# PotsDuino.net
KiCad netlist of a schematic drawn in Altium Designer
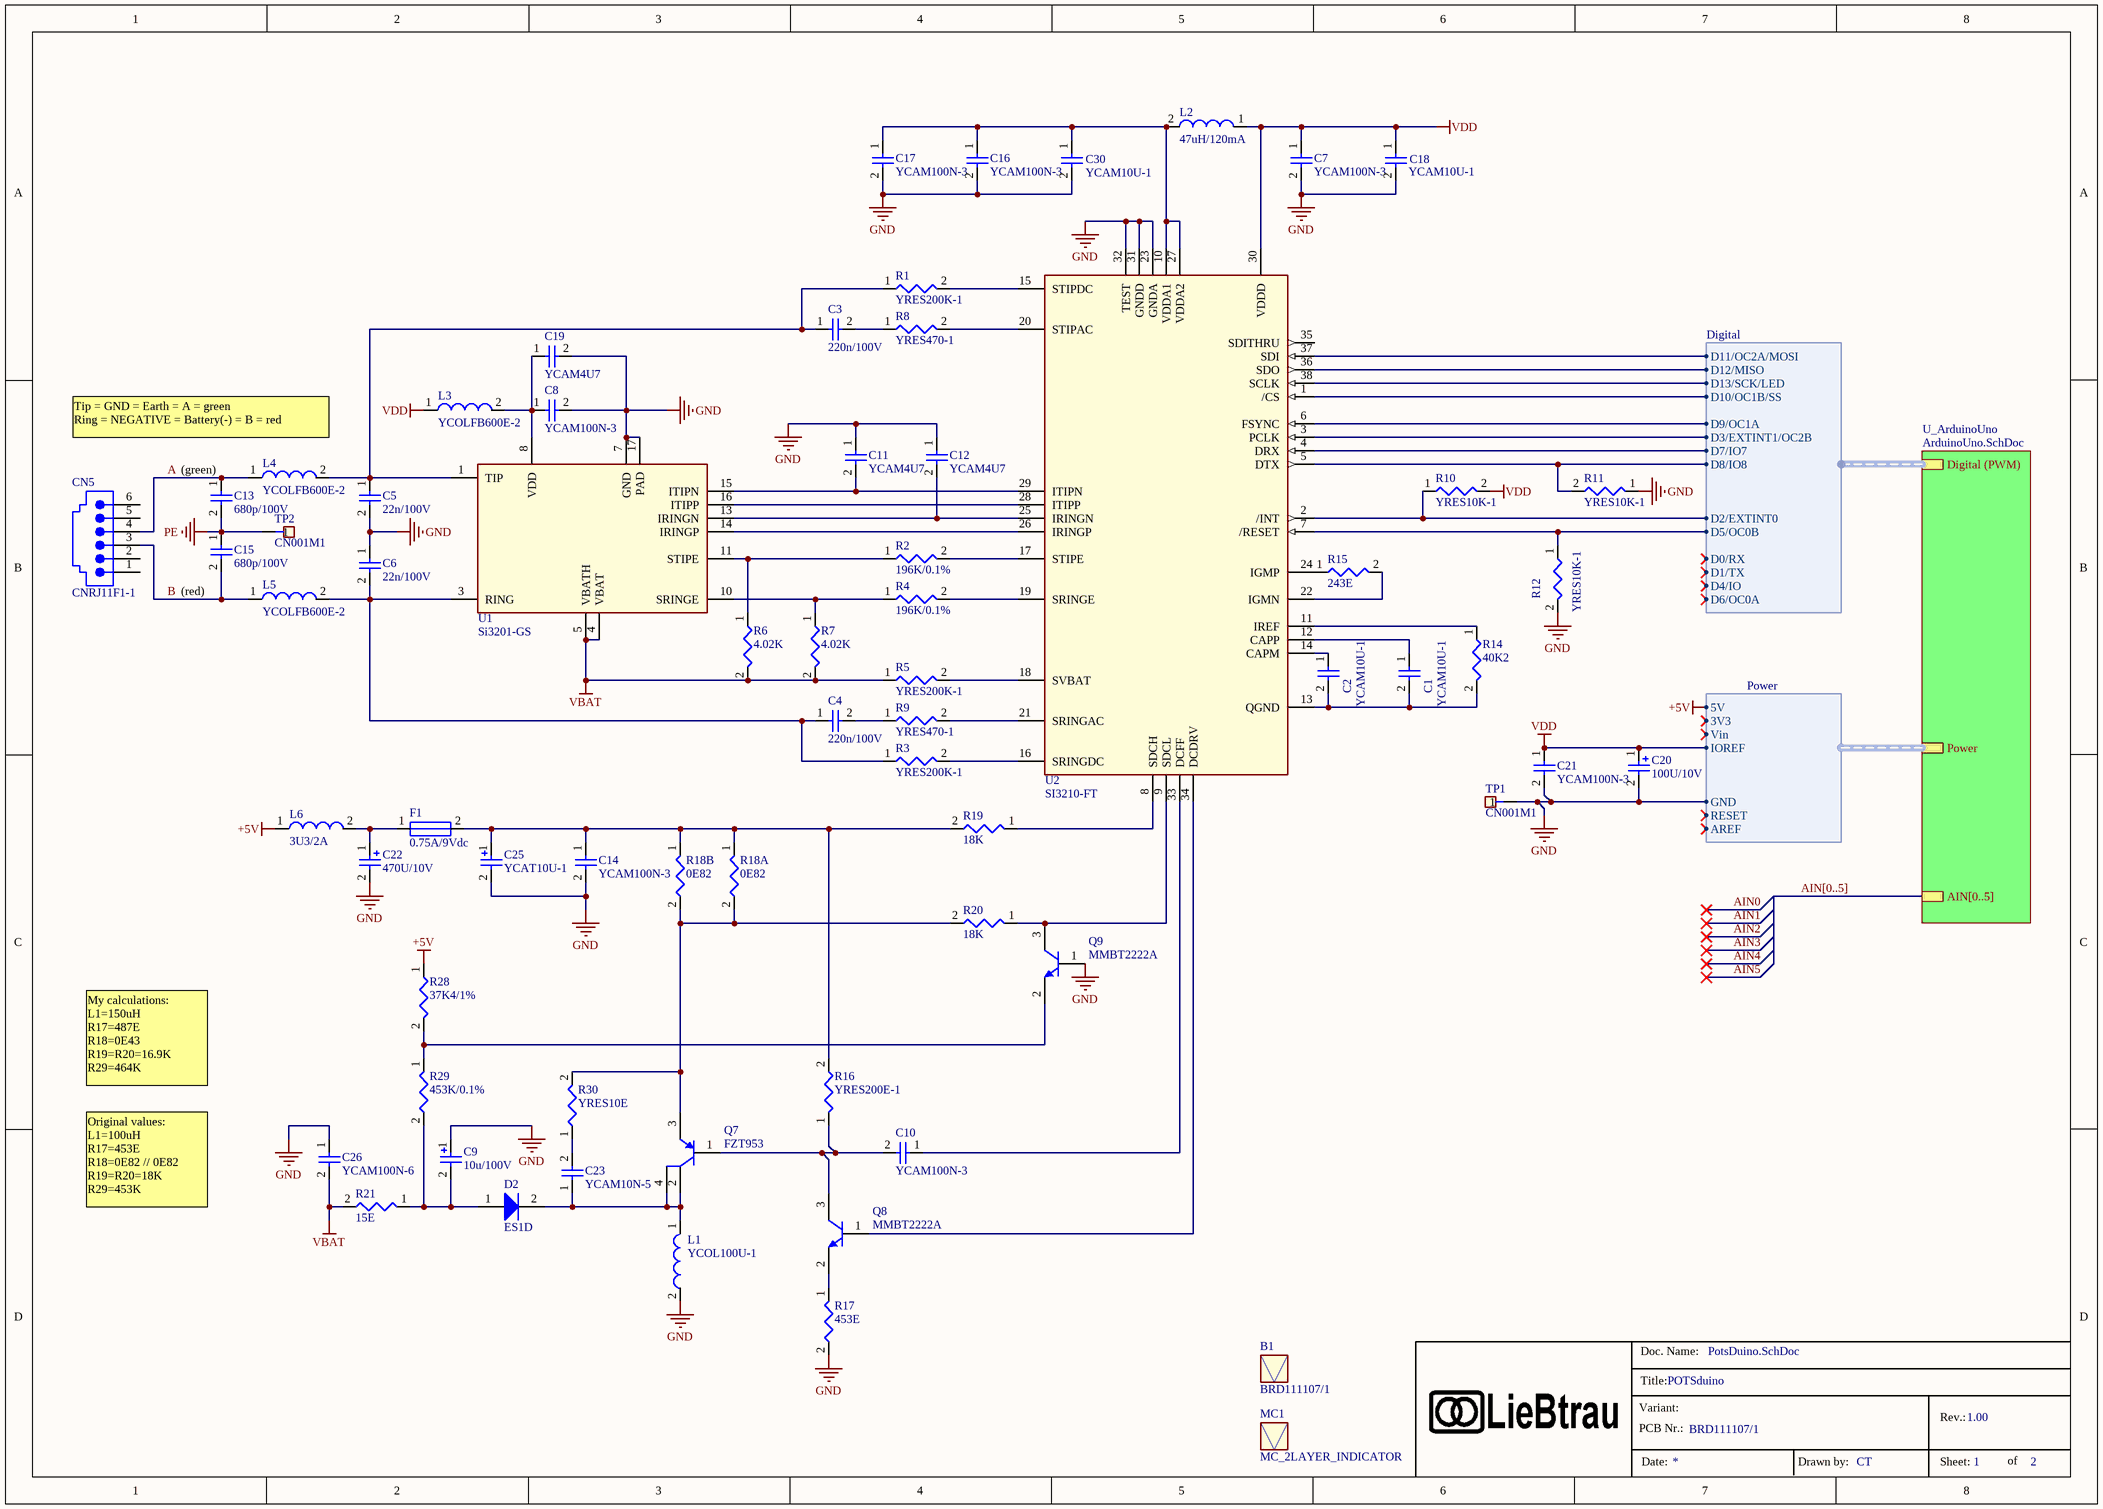
[diagram p0: PotsDuino.SchDoc]

(export (version "E")
  (design (tool "Eeschema 10.0.6"))
  (components
    (comp (ref "B1")
      (value "~")
      (footprint "=PCB_Nr")
      (fields (field (name "PART NUMBER") "BARE_PCB"))
      (libsource (lib "Testing") (part "BD_PCB"))
    )
    (comp (ref "C1") (value "YCAM10U-1") (footprint "CA_0805") (libsource (lib "Testing") (part "CA_NONPOL")))
    (comp (ref "C2") (value "YCAM10U-1") (footprint "CA_0805") (libsource (lib "Testing") (part "CA_NONPOL")))
    (comp (ref "C3")
      (value "220n/100V")
      (footprint "CA_0805")
      (fields (field (name "PART NUMBER") "MCCA000493") (field (name "MANUFACTURER") "Multicomp"))
      (libsource (lib "Testing") (part "CA_NONPOL"))
    )
    (comp (ref "C4")
      (value "220n/100V")
      (footprint "CA_0805")
      (fields (field (name "PART NUMBER") "MCCA000493") (field (name "MANUFACTURER") "Multicomp"))
      (libsource (lib "Testing") (part "CA_NONPOL"))
    )
    (comp (ref "C5")
      (value "22n/100V")
      (footprint "CA_0603")
      (fields (field (name "PART NUMBER") "C0603C223K1RACTU") (field (name "MANUFACTURER") "Kemet"))
      (libsource (lib "Testing") (part "CA_NONPOL"))
    )
    (comp (ref "C6")
      (value "22n/100V")
      (footprint "CA_0603")
      (fields (field (name "PART NUMBER") "C0603C223K1RACTU") (field (name "MANUFACTURER") "Kemet"))
      (libsource (lib "Testing") (part "CA_NONPOL"))
    )
    (comp (ref "C7")
      (value "YCAM100N-3")
      (footprint "CA_0603")
      (libsource (lib "Testing") (part "CA_NONPOL"))
    )
    (comp (ref "C8")
      (value "YCAM100N-3")
      (footprint "CA_0603")
      (libsource (lib "Testing") (part "CA_NONPOL"))
    )
    (comp (ref "C9")
      (value "10u/100V")
      (footprint "CA_CANTHD63P25_H110_R")
      (fields (field (name "PART NUMBER") "100YXF10MEFC6.3X11") (field (name "MANUFACTURER") "Rubycon"))
      (libsource (lib "Testing") (part "CA_POL"))
    )
    (comp (ref "C10")
      (value "YCAM100N-3")
      (footprint "CA_0603")
      (libsource (lib "Testing") (part "CA_NONPOL"))
    )
    (comp (ref "C11") (value "YCAM4U7") (footprint "CA_1206") (libsource (lib "Testing") (part "CA_NONPOL")))
    (comp (ref "C12") (value "YCAM4U7") (footprint "CA_1206") (libsource (lib "Testing") (part "CA_NONPOL")))
    (comp (ref "C13")
      (value "680p/100V")
      (footprint "CA_0603")
      (fields (field (name "PART NUMBER") "C0603C681J1GACTU") (field (name "MANUFACTURER") "Kemet"))
      (libsource (lib "Testing") (part "CA_NONPOL"))
    )
    (comp (ref "C14")
      (value "YCAM100N-3")
      (footprint "CA_0603")
      (libsource (lib "Testing") (part "CA_NONPOL"))
    )
    (comp (ref "C15")
      (value "680p/100V")
      (footprint "CA_0603")
      (fields (field (name "PART NUMBER") "C0603C681J1GACTU") (field (name "MANUFACTURER") "Kemet"))
      (libsource (lib "Testing") (part "CA_NONPOL"))
    )
    (comp (ref "C16")
      (value "YCAM100N-3")
      (footprint "CA_0603")
      (libsource (lib "Testing") (part "CA_NONPOL"))
    )
    (comp (ref "C17")
      (value "YCAM100N-3")
      (footprint "CA_0603")
      (libsource (lib "Testing") (part "CA_NONPOL"))
    )
    (comp (ref "C18")
      (value "YCAM10U-1")
      (footprint "CA_0805")
      (libsource (lib "Testing") (part "CA_NONPOL"))
    )
    (comp (ref "C19") (value "YCAM4U7") (footprint "CA_1206") (libsource (lib "Testing") (part "CA_NONPOL")))
    (comp (ref "C20")
      (value "100U/10V")
      (footprint "CA_CANTHD50P20_H110")
      (fields (field (name "PART NUMBER") "MCGPR10V107M5X11") (field (name "MANUFACTURER") "Multicomp"))
      (libsource (lib "Testing") (part "CA_POL"))
    )
    (comp (ref "C21")
      (value "YCAM100N-3")
      (footprint "CA_0603")
      (libsource (lib "Testing") (part "CA_NONPOL"))
    )
    (comp (ref "C22")
      (value "470U/10V")
      (footprint "CA_CANTHD80P35_H110")
      (fields (field (name "PART NUMBER") "MCGPR10V477M8X11") (field (name "MANUFACTURER") "Multicomp"))
      (libsource (lib "Testing") (part "CA_POL"))
    )
    (comp (ref "C23")
      (value "YCAM10N-5")
      (footprint "CA_1206")
      (fields (field (name "MANUFACTURER") "Yageo (Phycomp)"))
      (libsource (lib "Testing") (part "CA_NONPOL"))
    )
    (comp (ref "C25")
      (value "YCAT10U-1")
      (footprint "CA_1210_H21")
      (libsource (lib "Testing") (part "CA_POL"))
    )
    (comp (ref "C26")
      (value "YCAM100N-6")
      (footprint "CA_0805")
      (libsource (lib "Testing") (part "CA_NONPOL"))
    )
    (comp (ref "C30")
      (value "YCAM10U-1")
      (footprint "CA_0805")
      (libsource (lib "Testing") (part "CA_NONPOL"))
    )
    (comp (ref "CN5")
      (value "CNRJ11F1-1")
      (footprint "CN_MODJACK_6P")
      (libsource (lib "Testing") (part "CN_MODJACK_6P"))
    )
    (comp (ref "D2")
      (value "ES1D")
      (footprint "DI_DO-214AC")
      (description "1 Amp General Purpose Rectifier")
      (fields (field (name "MANUFACTURER") "Fairchild Semiconductor"))
      (libsource (lib "Testing") (part "DI_DIODE"))
    )
    (comp (ref "F1")
      (value "0.75A/9Vdc")
      (footprint "RE_0805")
      (fields (field (name "PART NUMBER") "MC36210") (field (name "MANUFACTURER") "Multicomp"))
      (libsource (lib "Testing") (part "FU_FUSE"))
    )
    (comp (ref "L1")
      (value "YCOL100U-1")
      (footprint "CL_WE-PD4")
      (fields (field (name "MANUFACTURER") "Wuerth Elektronik"))
      (libsource (lib "Testing") (part "CL_COIL"))
    )
    (comp (ref "L2")
      (value "47uH/120mA")
      (footprint "CL_0805")
      (fields (field (name "PART NUMBER") "L0805C470MDWIT") (field (name "MANUFACTURER") "Kemet"))
      (libsource (lib "Testing") (part "CL_COIL"))
    )
    (comp (ref "L3")
      (value "YCOLFB600E-2")
      (footprint "CL_0603")
      (fields (field (name "MANUFACTURER") "Murata"))
      (libsource (lib "") (part "CL_COIL_1"))
    )
    (comp (ref "L4")
      (value "YCOLFB600E-2")
      (footprint "CL_0603")
      (fields (field (name "MANUFACTURER") "Murata"))
      (libsource (lib "") (part "CL_COIL_1"))
    )
    (comp (ref "L5")
      (value "YCOLFB600E-2")
      (footprint "CL_0603")
      (fields (field (name "MANUFACTURER") "Murata"))
      (libsource (lib "") (part "CL_COIL_1"))
    )
    (comp (ref "L6")
      (value "3U3/2A")
      (footprint "CL_BOURNS_SDR0604_58x60")
      (fields (field (name "PART NUMBER") "MCSDC0604-3R3MU") (field (name "MANUFACTURER") "Multicomp"))
      (libsource (lib "") (part "CL_COIL_1"))
    )
    (comp (ref "MC1")
      (value "MC_2LAYER_INDICATOR")
      (footprint "MC_2LAYER_INDICATOR")
      (libsource (lib "Testing") (part "MC_MechPart_No_BOM"))
    )
    (comp (ref "Q7")
      (value "FZT953")
      (footprint "SC_SOT223")
      (description "Amplifier Transistor NPN Silicon")
      (fields (field (name "MANUFACTURER") "Diodes Inc."))
      (libsource (lib "Testing") (part "TR_PNP_1"))
    )
    (comp (ref "Q8")
      (value "MMBT2222A")
      (footprint "SC_SOT23")
      (description "Amplifier Transistor NPN Silicon")
      (fields (field (name "MANUFACTURER") "Fairchild Semiconductor"))
      (libsource (lib "Testing") (part "TR_NPN_1"))
    )
    (comp (ref "Q9")
      (value "MMBT2222A")
      (footprint "SC_SOT23")
      (description "Amplifier Transistor NPN Silicon")
      (fields (field (name "MANUFACTURER") "Fairchild Semiconductor"))
      (libsource (lib "Testing") (part "TR_NPN_1"))
    )
    (comp (ref "R1")
      (value "YRES200K-1")
      (footprint "RE_0603")
      (description "Resistor")
      (libsource (lib "Testing") (part "RE_RES"))
    )
    (comp (ref "R2")
      (value "196K/0.1%")
      (footprint "RE_0603")
      (description "Resistor")
      (fields
        (field (name "PART NUMBER") "ERA3AEB1963V")
        (field (name "MANUFACTURER") "Panasonic Electronic Components")
      )
      (libsource (lib "Testing") (part "RE_RES"))
    )
    (comp (ref "R3")
      (value "YRES200K-1")
      (footprint "RE_0603")
      (description "Resistor")
      (libsource (lib "Testing") (part "RE_RES"))
    )
    (comp (ref "R4")
      (value "196K/0.1%")
      (footprint "RE_0603")
      (description "Resistor")
      (fields
        (field (name "PART NUMBER") "ERA3AEB1963V")
        (field (name "MANUFACTURER") "Panasonic Electronic Components")
      )
      (libsource (lib "Testing") (part "RE_RES"))
    )
    (comp (ref "R5")
      (value "YRES200K-1")
      (footprint "RE_0603")
      (description "Resistor")
      (libsource (lib "Testing") (part "RE_RES"))
    )
    (comp (ref "R6")
      (value "4.02K")
      (footprint "RE_1206")
      (description "Resistor")
      (fields (field (name "PART NUMBER") "CRCW12064K02FKEA") (field (name "MANUFACTURER") "Vishay Draloric"))
      (libsource (lib "Testing") (part "RE_RES"))
    )
    (comp (ref "R7")
      (value "4.02K")
      (footprint "RE_1206")
      (description "Resistor")
      (fields (field (name "PART NUMBER") "CRCW12064K02FKEA") (field (name "MANUFACTURER") "Vishay Draloric"))
      (libsource (lib "Testing") (part "RE_RES"))
    )
    (comp (ref "R8")
      (value "YRES470-1")
      (footprint "RE_0603")
      (description "Resistor")
      (libsource (lib "Testing") (part "RE_RES"))
    )
    (comp (ref "R9")
      (value "YRES470-1")
      (footprint "RE_0603")
      (description "Resistor")
      (libsource (lib "Testing") (part "RE_RES"))
    )
    (comp (ref "R10")
      (value "YRES10K-1")
      (footprint "RE_0603")
      (description "Resistor")
      (libsource (lib "Testing") (part "RE_RES"))
    )
    (comp (ref "R11")
      (value "YRES10K-1")
      (footprint "RE_0603")
      (description "Resistor")
      (libsource (lib "Testing") (part "RE_RES"))
    )
    (comp (ref "R12")
      (value "YRES10K-1")
      (footprint "RE_0603")
      (description "Resistor")
      (libsource (lib "Testing") (part "RE_RES"))
    )
    (comp (ref "R14")
      (value "40K2")
      (footprint "RE_0603")
      (description "Resistor")
      (fields (field (name "PART NUMBER") "MC 0.063W 0603 1% 40K2") (field (name "MANUFACTURER") "Multicomp"))
      (libsource (lib "Testing") (part "RE_RES"))
    )
    (comp (ref "R15")
      (value "243E")
      (footprint "RE_0603")
      (description "Resistor")
      (fields (field (name "PART NUMBER") "MC 0.063W 0603 1% 243R") (field (name "MANUFACTURER") "Multicomp"))
      (libsource (lib "Testing") (part "RE_RES"))
    )
    (comp (ref "R16")
      (value "YRES200E-1")
      (footprint "RE_0603")
      (description "Resistor")
      (libsource (lib "Testing") (part "RE_RES"))
    )
    (comp (ref "R17")
      (value "453E")
      (footprint "RE_0805")
      (description "Resistor")
      (fields (field (name "PART NUMBER") "MCTC0525B4530T5E") (field (name "MANUFACTURER") "Multicomp"))
      (libsource (lib "Testing") (part "RE_RES"))
    )
    (comp (ref "R18A")
      (value "0E82")
      (footprint "RE_0805")
      (description "Resistor")
      (fields
        (field (name "PART NUMBER") "ERJ6RQFR82V")
        (field (name "MANUFACTURER") "Panasonic Electronic Components")
      )
      (libsource (lib "Testing") (part "RE_RES"))
    )
    (comp (ref "R18B")
      (value "0E82")
      (footprint "RE_0805")
      (description "Resistor")
      (fields
        (field (name "PART NUMBER") "ERJ6RQFR82V")
        (field (name "MANUFACTURER") "Panasonic Electronic Components")
      )
      (libsource (lib "Testing") (part "RE_RES"))
    )
    (comp (ref "R19")
      (value "18K")
      (footprint "RE_0603")
      (description "Resistor")
      (fields (field (name "PART NUMBER") "SG73S1JTTD1802F") (field (name "MANUFACTURER") "KOA"))
      (libsource (lib "Testing") (part "RE_RES"))
    )
    (comp (ref "R20")
      (value "18K")
      (footprint "RE_0603")
      (description "Resistor")
      (fields (field (name "PART NUMBER") "SG73S1JTTD1802F") (field (name "MANUFACTURER") "KOA"))
      (libsource (lib "Testing") (part "RE_RES"))
    )
    (comp (ref "R21")
      (value "15E")
      (footprint "RE_0805")
      (description "Resistor")
      (fields (field (name "PART NUMBER") "SG73P2ATTD15R0F") (field (name "MANUFACTURER") "KOA"))
      (libsource (lib "Testing") (part "RE_RES"))
    )
    (comp (ref "R28")
      (value "37K4/1%")
      (footprint "RE_1206")
      (description "Resistor")
      (fields (field (name "PART NUMBER") "CRCW120637K4FKEA") (field (name "MANUFACTURER") "Vishay Draloric"))
      (libsource (lib "Testing") (part "RE_RES"))
    )
    (comp (ref "R29")
      (value "453K/0.1%")
      (footprint "RE_0805")
      (description "Resistor")
      (fields (field (name "PART NUMBER") "MCTC0525B4533T5E") (field (name "MANUFACTURER") "Multicomp"))
      (libsource (lib "Testing") (part "RE_RES"))
    )
    (comp (ref "R30")
      (value "YRES10E")
      (footprint "RE_1206")
      (description "Resistor")
      (fields (field (name "MANUFACTURER") "Vishay Draloric"))
      (libsource (lib "Testing") (part "RE_RES"))
    )
    (comp (ref "TP1")
      (value "CN001M1")
      (footprint "CN_TP_TH_1.3mm")
      (libsource (lib "Testing") (part "CN_TESTPIN"))
    )
    (comp (ref "TP2")
      (value "CN001M1")
      (footprint "CN_TP_TH_1.3mm")
      (libsource (lib "") (part "CN_TESTPIN_1"))
    )
    (comp (ref "U1")
      (value "Si3201-GS")
      (footprint "SC_ESOIC16")
      (fields (field (name "MANUFACTURER") "Silicon Labs"))
      (libsource (lib "Testing") (part "IC_Si3201"))
    )
    (comp (ref "U2")
      (value "SI3210-FT")
      (footprint "SC_TSSOP38")
      (fields (field (name "MANUFACTURER") "Silicon Labs"))
      (libsource (lib "Testing") (part "IC_Si3210"))
    )
  )
  (nets
    (net (code "3") (name "+5V") (class "Default")
      (node (ref "L6") (pin "1") (pinfunction "1_1") (pintype "passive"))
      (node (ref "R28") (pin "1") (pinfunction "1_1") (pintype "passive"))
    )
    (net (code "4") (name "/A") (class "Default")
      (node (ref "C13") (pin "1") (pinfunction "1_1") (pintype "passive"))
      (node (ref "CN5") (pin "4") (pinfunction "4_4") (pintype "passive"))
      (node (ref "L4") (pin "1") (pinfunction "1_1") (pintype "passive"))
    )
    (net (code "12") (name "/B") (class "Default")
      (node (ref "C15") (pin "2") (pinfunction "2_2") (pintype "passive"))
      (node (ref "CN5") (pin "3") (pinfunction "3_3") (pintype "passive"))
      (node (ref "L5") (pin "1") (pinfunction "1_1") (pintype "passive"))
    )
    (net (code "13") (name "/D2{slash}EXTINT0") (class "Default")
      (node (ref "R10") (pin "1") (pinfunction "1_1") (pintype "passive"))
      (node (ref "U2") (pin "2") (pinfunction "/INT_2") (pintype "output"))
    )
    (net (code "14") (name "/D3{slash}EXTINT1{slash}OC2B") (class "Default")
      (node (ref "U2") (pin "3") (pinfunction "PCLK_3") (pintype "input"))
    )
    (net (code "15") (name "/D5{slash}OC0B") (class "Default")
      (node (ref "R12") (pin "1") (pinfunction "1_1") (pintype "passive"))
      (node (ref "U2") (pin "7") (pinfunction "/RESET_7") (pintype "input"))
    )
    (net (code "16") (name "/D7{slash}IO7") (class "Default")
      (node (ref "U2") (pin "4") (pinfunction "DRX_4") (pintype "input"))
    )
    (net (code "17") (name "/D8{slash}IO8") (class "Default")
      (node (ref "R11") (pin "2") (pinfunction "2_2") (pintype "passive"))
      (node (ref "U2") (pin "5") (pinfunction "DTX_5") (pintype "output"))
    )
    (net (code "18") (name "/D9{slash}OC1A") (class "Default")
      (node (ref "U2") (pin "6") (pinfunction "FSYNC_6") (pintype "input"))
    )
    (net (code "19") (name "/D10{slash}OC1B{slash}SS") (class "Default")
      (node (ref "U2") (pin "1") (pinfunction "/CS_1") (pintype "input"))
    )
    (net (code "20") (name "/D11{slash}OC2A{slash}MOSI") (class "Default")
      (node (ref "U2") (pin "37") (pinfunction "SDI_37") (pintype "input"))
    )
    (net (code "21") (name "/D12{slash}MISO") (class "Default")
      (node (ref "U2") (pin "36") (pinfunction "SDO_36") (pintype "output"))
    )
    (net (code "22") (name "/D13{slash}SCK{slash}LED") (class "Default")
      (node (ref "U2") (pin "38") (pinfunction "SCLK_38") (pintype "input"))
    )
    (net (code "25") (name "GND") (class "Default")
      (node (ref "C11") (pin "1") (pinfunction "1_1") (pintype "passive"))
      (node (ref "C12") (pin "1") (pinfunction "1_1") (pintype "passive"))
      (node (ref "C14") (pin "2") (pinfunction "2_2") (pintype "passive"))
      (node (ref "C16") (pin "2") (pinfunction "2_2") (pintype "passive"))
      (node (ref "C17") (pin "2") (pinfunction "2_2") (pintype "passive"))
      (node (ref "C18") (pin "2") (pinfunction "2_2") (pintype "passive"))
      (node (ref "C19") (pin "2") (pinfunction "2_2") (pintype "passive"))
      (node (ref "C20") (pin "2") (pinfunction "2_2") (pintype "passive"))
      (node (ref "C21") (pin "2") (pinfunction "2_2") (pintype "passive"))
      (node (ref "C22") (pin "2") (pinfunction "2_2") (pintype "passive"))
      (node (ref "C25") (pin "2") (pinfunction "2_2") (pintype "passive"))
      (node (ref "C26") (pin "1") (pinfunction "1_1") (pintype "passive"))
      (node (ref "C30") (pin "2") (pinfunction "2_2") (pintype "passive"))
      (node (ref "C5") (pin "2") (pinfunction "2_2") (pintype "passive"))
      (node (ref "C6") (pin "1") (pinfunction "1_1") (pintype "passive"))
      (node (ref "C7") (pin "2") (pinfunction "2_2") (pintype "passive"))
      (node (ref "C8") (pin "2") (pinfunction "2_2") (pintype "passive"))
      (node (ref "C9") (pin "1") (pinfunction "1_1") (pintype "passive"))
      (node (ref "L1") (pin "2") (pinfunction "2_2") (pintype "passive"))
      (node (ref "Q9") (pin "1") (pinfunction "C_1") (pintype "passive"))
      (node (ref "R11") (pin "1") (pinfunction "1_1") (pintype "passive"))
      (node (ref "R12") (pin "2") (pinfunction "2_2") (pintype "passive"))
      (node (ref "R17") (pin "2") (pinfunction "2_2") (pintype "passive"))
      (node (ref "TP1") (pin "1") (pinfunction "1_1") (pintype "passive"))
      (node (ref "U1") (pin "17") (pinfunction "PAD_17") (pintype "passive"))
      (node (ref "U1") (pin "7") (pinfunction "GND_7") (pintype "passive"))
      (node (ref "U2") (pin "23") (pinfunction "GNDA_23") (pintype "passive"))
      (node (ref "U2") (pin "31") (pinfunction "GNDD_31") (pintype "passive"))
      (node (ref "U2") (pin "32") (pinfunction "TEST_32") (pintype "passive"))
    )
    (net (code "26") (name "Net-(C3-Pad2)") (class "Default")
      (node (ref "C3") (pin "2") (pinfunction "2_2") (pintype "passive"))
      (node (ref "R8") (pin "1") (pinfunction "1_1") (pintype "passive"))
    )
    (net (code "27") (name "Net-(C4-Pad2)") (class "Default")
      (node (ref "C4") (pin "2") (pinfunction "2_2") (pintype "passive"))
      (node (ref "R9") (pin "1") (pinfunction "1_1") (pintype "passive"))
    )
    (net (code "28") (name "Net-(C14-Pad1)") (class "Default")
      (node (ref "C14") (pin "1") (pinfunction "1_1") (pintype "passive"))
      (node (ref "C25") (pin "1") (pinfunction "1_1") (pintype "passive"))
      (node (ref "F1") (pin "2") (pinfunction "2_2") (pintype "passive"))
      (node (ref "R16") (pin "2") (pinfunction "2_2") (pintype "passive"))
      (node (ref "R18A") (pin "1") (pinfunction "1_1") (pintype "passive"))
      (node (ref "R18B") (pin "1") (pinfunction "1_1") (pintype "passive"))
      (node (ref "R19") (pin "2") (pinfunction "2_2") (pintype "passive"))
    )
    (net (code "29") (name "Net-(C22-Pad1)") (class "Default")
      (node (ref "C22") (pin "1") (pinfunction "1_1") (pintype "passive"))
      (node (ref "F1") (pin "1") (pinfunction "1_1") (pintype "passive"))
      (node (ref "L6") (pin "2") (pinfunction "2_2") (pintype "passive"))
    )
    (net (code "30") (name "Net-(C23-Pad2)") (class "Default")
      (node (ref "C23") (pin "2") (pinfunction "2_2") (pintype "passive"))
      (node (ref "R30") (pin "1") (pinfunction "1_1") (pintype "passive"))
    )
    (net (code "31") (name "Net-(D2-A)") (class "Default")
      (node (ref "C9") (pin "2") (pinfunction "2_2") (pintype "passive"))
      (node (ref "D2") (pin "1") (pinfunction "A_1") (pintype "passive"))
      (node (ref "R21") (pin "1") (pinfunction "1_1") (pintype "passive"))
      (node (ref "R29") (pin "2") (pinfunction "2_2") (pintype "passive"))
    )
    (net (code "32") (name "Net-(D2-K)") (class "Default")
      (node (ref "C23") (pin "1") (pinfunction "1_1") (pintype "passive"))
      (node (ref "D2") (pin "2") (pinfunction "K_2") (pintype "passive"))
      (node (ref "L1") (pin "1") (pinfunction "1_1") (pintype "passive"))
      (node (ref "Q7") (pin "2") (pinfunction "B_2") (pintype "passive"))
      (node (ref "Q7") (pin "4") (pinfunction "4_4") (pintype "passive"))
    )
    (net (code "33") (name "Net-(Q7-C)") (class "Default")
      (node (ref "C10") (pin "2") (pinfunction "2_2") (pintype "passive"))
      (node (ref "Q7") (pin "1") (pinfunction "C_1") (pintype "passive"))
      (node (ref "Q8") (pin "3") (pinfunction "E_3") (pintype "passive"))
      (node (ref "R16") (pin "1") (pinfunction "1_1") (pintype "passive"))
    )
    (net (code "34") (name "Net-(Q7-E)") (class "Default")
      (node (ref "Q7") (pin "3") (pinfunction "E_3") (pintype "passive"))
      (node (ref "R18A") (pin "2") (pinfunction "2_2") (pintype "passive"))
      (node (ref "R18B") (pin "2") (pinfunction "2_2") (pintype "passive"))
      (node (ref "R20") (pin "2") (pinfunction "2_2") (pintype "passive"))
      (node (ref "R30") (pin "2") (pinfunction "2_2") (pintype "passive"))
    )
    (net (code "35") (name "Net-(Q8-B)") (class "Default")
      (node (ref "Q8") (pin "2") (pinfunction "B_2") (pintype "passive"))
      (node (ref "R17") (pin "1") (pinfunction "1_1") (pintype "passive"))
    )
    (net (code "36") (name "Net-(Q8-C)") (class "Default")
      (node (ref "Q8") (pin "1") (pinfunction "C_1") (pintype "passive"))
      (node (ref "U2") (pin "34") (pinfunction "DCDRV_34") (pintype "passive"))
    )
    (net (code "37") (name "Net-(Q9-B)") (class "Default")
      (node (ref "Q9") (pin "2") (pinfunction "B_2") (pintype "passive"))
      (node (ref "R28") (pin "2") (pinfunction "2_2") (pintype "passive"))
      (node (ref "R29") (pin "1") (pinfunction "1_1") (pintype "passive"))
    )
    (net (code "38") (name "Net-(Q9-E)") (class "Default")
      (node (ref "Q9") (pin "3") (pinfunction "E_3") (pintype "passive"))
      (node (ref "R20") (pin "1") (pinfunction "1_1") (pintype "passive"))
      (node (ref "U2") (pin "9") (pinfunction "SDCL_9") (pintype "passive"))
    )
    (net (code "39") (name "Net-(U1-IRINGN)") (class "Default")
      (node (ref "C12") (pin "2") (pinfunction "2_2") (pintype "passive"))
      (node (ref "U1") (pin "13") (pinfunction "IRINGN_13") (pintype "passive"))
      (node (ref "U2") (pin "25") (pinfunction "IRINGN_25") (pintype "passive"))
    )
    (net (code "40") (name "Net-(U1-IRINGP)") (class "Default")
      (node (ref "U1") (pin "14") (pinfunction "IRINGP_14") (pintype "passive"))
      (node (ref "U2") (pin "26") (pinfunction "IRINGP_26") (pintype "passive"))
    )
    (net (code "41") (name "Net-(U1-ITIPN)") (class "Default")
      (node (ref "C11") (pin "2") (pinfunction "2_2") (pintype "passive"))
      (node (ref "U1") (pin "15") (pinfunction "ITIPN_15") (pintype "passive"))
      (node (ref "U2") (pin "29") (pinfunction "ITIPN_29") (pintype "passive"))
    )
    (net (code "42") (name "Net-(U1-ITIPP)") (class "Default")
      (node (ref "U1") (pin "16") (pinfunction "ITIPP_16") (pintype "passive"))
      (node (ref "U2") (pin "28") (pinfunction "ITIPP_28") (pintype "passive"))
    )
    (net (code "43") (name "Net-(U1-RING)") (class "Default")
      (node (ref "C4") (pin "1") (pinfunction "1_1") (pintype "passive"))
      (node (ref "C6") (pin "2") (pinfunction "2_2") (pintype "passive"))
      (node (ref "L5") (pin "2") (pinfunction "2_2") (pintype "passive"))
      (node (ref "R3") (pin "1") (pinfunction "1_1") (pintype "passive"))
      (node (ref "U1") (pin "3") (pinfunction "RING_3") (pintype "passive"))
    )
    (net (code "44") (name "Net-(U1-SRINGE)") (class "Default")
      (node (ref "R4") (pin "1") (pinfunction "1_1") (pintype "passive"))
      (node (ref "R7") (pin "1") (pinfunction "1_1") (pintype "passive"))
      (node (ref "U1") (pin "10") (pinfunction "SRINGE_10") (pintype "passive"))
    )
    (net (code "45") (name "Net-(U1-STIPE)") (class "Default")
      (node (ref "R2") (pin "1") (pinfunction "1_1") (pintype "passive"))
      (node (ref "R6") (pin "1") (pinfunction "1_1") (pintype "passive"))
      (node (ref "U1") (pin "11") (pinfunction "STIPE_11") (pintype "passive"))
    )
    (net (code "46") (name "Net-(U1-TIP)") (class "Default")
      (node (ref "C3") (pin "1") (pinfunction "1_1") (pintype "passive"))
      (node (ref "C5") (pin "1") (pinfunction "1_1") (pintype "passive"))
      (node (ref "L4") (pin "2") (pinfunction "2_2") (pintype "passive"))
      (node (ref "R1") (pin "1") (pinfunction "1_1") (pintype "passive"))
      (node (ref "U1") (pin "1") (pinfunction "TIP_1") (pintype "passive"))
    )
    (net (code "47") (name "Net-(U1-VDD)") (class "Default")
      (node (ref "C19") (pin "1") (pinfunction "1_1") (pintype "passive"))
      (node (ref "C8") (pin "1") (pinfunction "1_1") (pintype "passive"))
      (node (ref "L3") (pin "2") (pinfunction "2_2") (pintype "passive"))
      (node (ref "U1") (pin "8") (pinfunction "VDD_8") (pintype "passive"))
    )
    (net (code "48") (name "Net-(U2-CAPM)") (class "Default")
      (node (ref "C2") (pin "1") (pinfunction "1_1") (pintype "passive"))
      (node (ref "U2") (pin "14") (pinfunction "CAPM_14") (pintype "passive"))
    )
    (net (code "49") (name "Net-(U2-CAPP)") (class "Default")
      (node (ref "C1") (pin "1") (pinfunction "1_1") (pintype "passive"))
      (node (ref "U2") (pin "12") (pinfunction "CAPP_12") (pintype "passive"))
    )
    (net (code "50") (name "Net-(U2-DCFF)") (class "Default")
      (node (ref "C10") (pin "1") (pinfunction "1_1") (pintype "passive"))
      (node (ref "U2") (pin "33") (pinfunction "DCFF_33") (pintype "passive"))
    )
    (net (code "51") (name "Net-(U2-IGMN)") (class "Default")
      (node (ref "R15") (pin "2") (pinfunction "2_2") (pintype "passive"))
      (node (ref "U2") (pin "22") (pinfunction "IGMN_22") (pintype "passive"))
    )
    (net (code "52") (name "Net-(U2-IGMP)") (class "Default")
      (node (ref "R15") (pin "1") (pinfunction "1_1") (pintype "passive"))
      (node (ref "U2") (pin "24") (pinfunction "IGMP_24") (pintype "passive"))
    )
    (net (code "53") (name "Net-(U2-IREF)") (class "Default")
      (node (ref "R14") (pin "1") (pinfunction "1_1") (pintype "passive"))
      (node (ref "U2") (pin "11") (pinfunction "IREF_11") (pintype "passive"))
    )
    (net (code "54") (name "Net-(U2-QGND)") (class "Default")
      (node (ref "C1") (pin "2") (pinfunction "2_2") (pintype "passive"))
      (node (ref "C2") (pin "2") (pinfunction "2_2") (pintype "passive"))
      (node (ref "R14") (pin "2") (pinfunction "2_2") (pintype "passive"))
      (node (ref "U2") (pin "13") (pinfunction "QGND_13") (pintype "passive"))
    )
    (net (code "55") (name "Net-(U2-SDCH)") (class "Default")
      (node (ref "R19") (pin "1") (pinfunction "1_1") (pintype "passive"))
      (node (ref "U2") (pin "8") (pinfunction "SDCH_8") (pintype "passive"))
    )
    (net (code "56") (name "Net-(U2-SRINGAC)") (class "Default")
      (node (ref "R9") (pin "2") (pinfunction "2_2") (pintype "passive"))
      (node (ref "U2") (pin "21") (pinfunction "SRINGAC_21") (pintype "passive"))
    )
    (net (code "57") (name "Net-(U2-SRINGDC)") (class "Default")
      (node (ref "R3") (pin "2") (pinfunction "2_2") (pintype "passive"))
      (node (ref "U2") (pin "16") (pinfunction "SRINGDC_16") (pintype "passive"))
    )
    (net (code "58") (name "Net-(U2-SRINGE)") (class "Default")
      (node (ref "R4") (pin "2") (pinfunction "2_2") (pintype "passive"))
      (node (ref "U2") (pin "19") (pinfunction "SRINGE_19") (pintype "passive"))
    )
    (net (code "59") (name "Net-(U2-STIPAC)") (class "Default")
      (node (ref "R8") (pin "2") (pinfunction "2_2") (pintype "passive"))
      (node (ref "U2") (pin "20") (pinfunction "STIPAC_20") (pintype "passive"))
    )
    (net (code "60") (name "Net-(U2-STIPDC)") (class "Default")
      (node (ref "R1") (pin "2") (pinfunction "2_2") (pintype "passive"))
      (node (ref "U2") (pin "15") (pinfunction "STIPDC_15") (pintype "passive"))
    )
    (net (code "61") (name "Net-(U2-STIPE)") (class "Default")
      (node (ref "R2") (pin "2") (pinfunction "2_2") (pintype "passive"))
      (node (ref "U2") (pin "17") (pinfunction "STIPE_17") (pintype "passive"))
    )
    (net (code "62") (name "Net-(U2-SVBAT)") (class "Default")
      (node (ref "R5") (pin "2") (pinfunction "2_2") (pintype "passive"))
      (node (ref "U2") (pin "18") (pinfunction "SVBAT_18") (pintype "passive"))
    )
    (net (code "63") (name "Net-(U2-VDDA1)") (class "Default")
      (node (ref "C16") (pin "1") (pinfunction "1_1") (pintype "passive"))
      (node (ref "C17") (pin "1") (pinfunction "1_1") (pintype "passive"))
      (node (ref "C30") (pin "1") (pinfunction "1_1") (pintype "passive"))
      (node (ref "L2") (pin "2") (pinfunction "2_2") (pintype "passive"))
      (node (ref "U2") (pin "10") (pinfunction "VDDA1_10") (pintype "passive"))
      (node (ref "U2") (pin "27") (pinfunction "VDDA2_27") (pintype "passive"))
    )
    (net (code "64") (name "PE") (class "Default")
      (node (ref "C13") (pin "2") (pinfunction "2_2") (pintype "passive"))
      (node (ref "C15") (pin "1") (pinfunction "1_1") (pintype "passive"))
      (node (ref "TP2") (pin "1") (pinfunction "1_1") (pintype "passive"))
    )
    (net (code "65") (name "VBAT") (class "Default")
      (node (ref "C26") (pin "2") (pinfunction "2_2") (pintype "passive"))
      (node (ref "R21") (pin "2") (pinfunction "2_2") (pintype "passive"))
      (node (ref "R5") (pin "1") (pinfunction "1_1") (pintype "passive"))
      (node (ref "R6") (pin "2") (pinfunction "2_2") (pintype "passive"))
      (node (ref "R7") (pin "2") (pinfunction "2_2") (pintype "passive"))
      (node (ref "U1") (pin "4") (pinfunction "VBAT_4") (pintype "passive"))
      (node (ref "U1") (pin "5") (pinfunction "VBATH_5") (pintype "passive"))
    )
    (net (code "66") (name "VDD") (class "Default")
      (node (ref "C18") (pin "1") (pinfunction "1_1") (pintype "passive"))
      (node (ref "C20") (pin "1") (pinfunction "1_1") (pintype "passive"))
      (node (ref "C21") (pin "1") (pinfunction "1_1") (pintype "passive"))
      (node (ref "C7") (pin "1") (pinfunction "1_1") (pintype "passive"))
      (node (ref "L2") (pin "1") (pinfunction "1_1") (pintype "passive"))
      (node (ref "L3") (pin "1") (pinfunction "1_1") (pintype "passive"))
      (node (ref "R10") (pin "2") (pinfunction "2_2") (pintype "passive"))
      (node (ref "U2") (pin "30") (pinfunction "VDDD_30") (pintype "passive"))
    )
    (net (code "67") (name "unconnected-(CN5-Pad1)") (class "Default")
      (node (ref "CN5") (pin "1") (pinfunction "1_1") (pintype "passive"))
    )
    (net (code "68") (name "unconnected-(CN5-Pad2)") (class "Default")
      (node (ref "CN5") (pin "2") (pinfunction "2_2") (pintype "passive"))
    )
    (net (code "69") (name "unconnected-(CN5-Pad5)") (class "Default")
      (node (ref "CN5") (pin "5") (pinfunction "5_5") (pintype "passive"))
    )
    (net (code "70") (name "unconnected-(CN5-Pad6)") (class "Default")
      (node (ref "CN5") (pin "6") (pinfunction "6_6") (pintype "passive"))
    )
    (net (code "71") (name "unconnected-(U2-SDITHRU-Pad35)") (class "Default")
      (node (ref "U2") (pin "35") (pinfunction "SDITHRU_35") (pintype "output"))
    )
  )
)
